# PDM.net
KiCad netlist of a schematic drawn in EAGLE
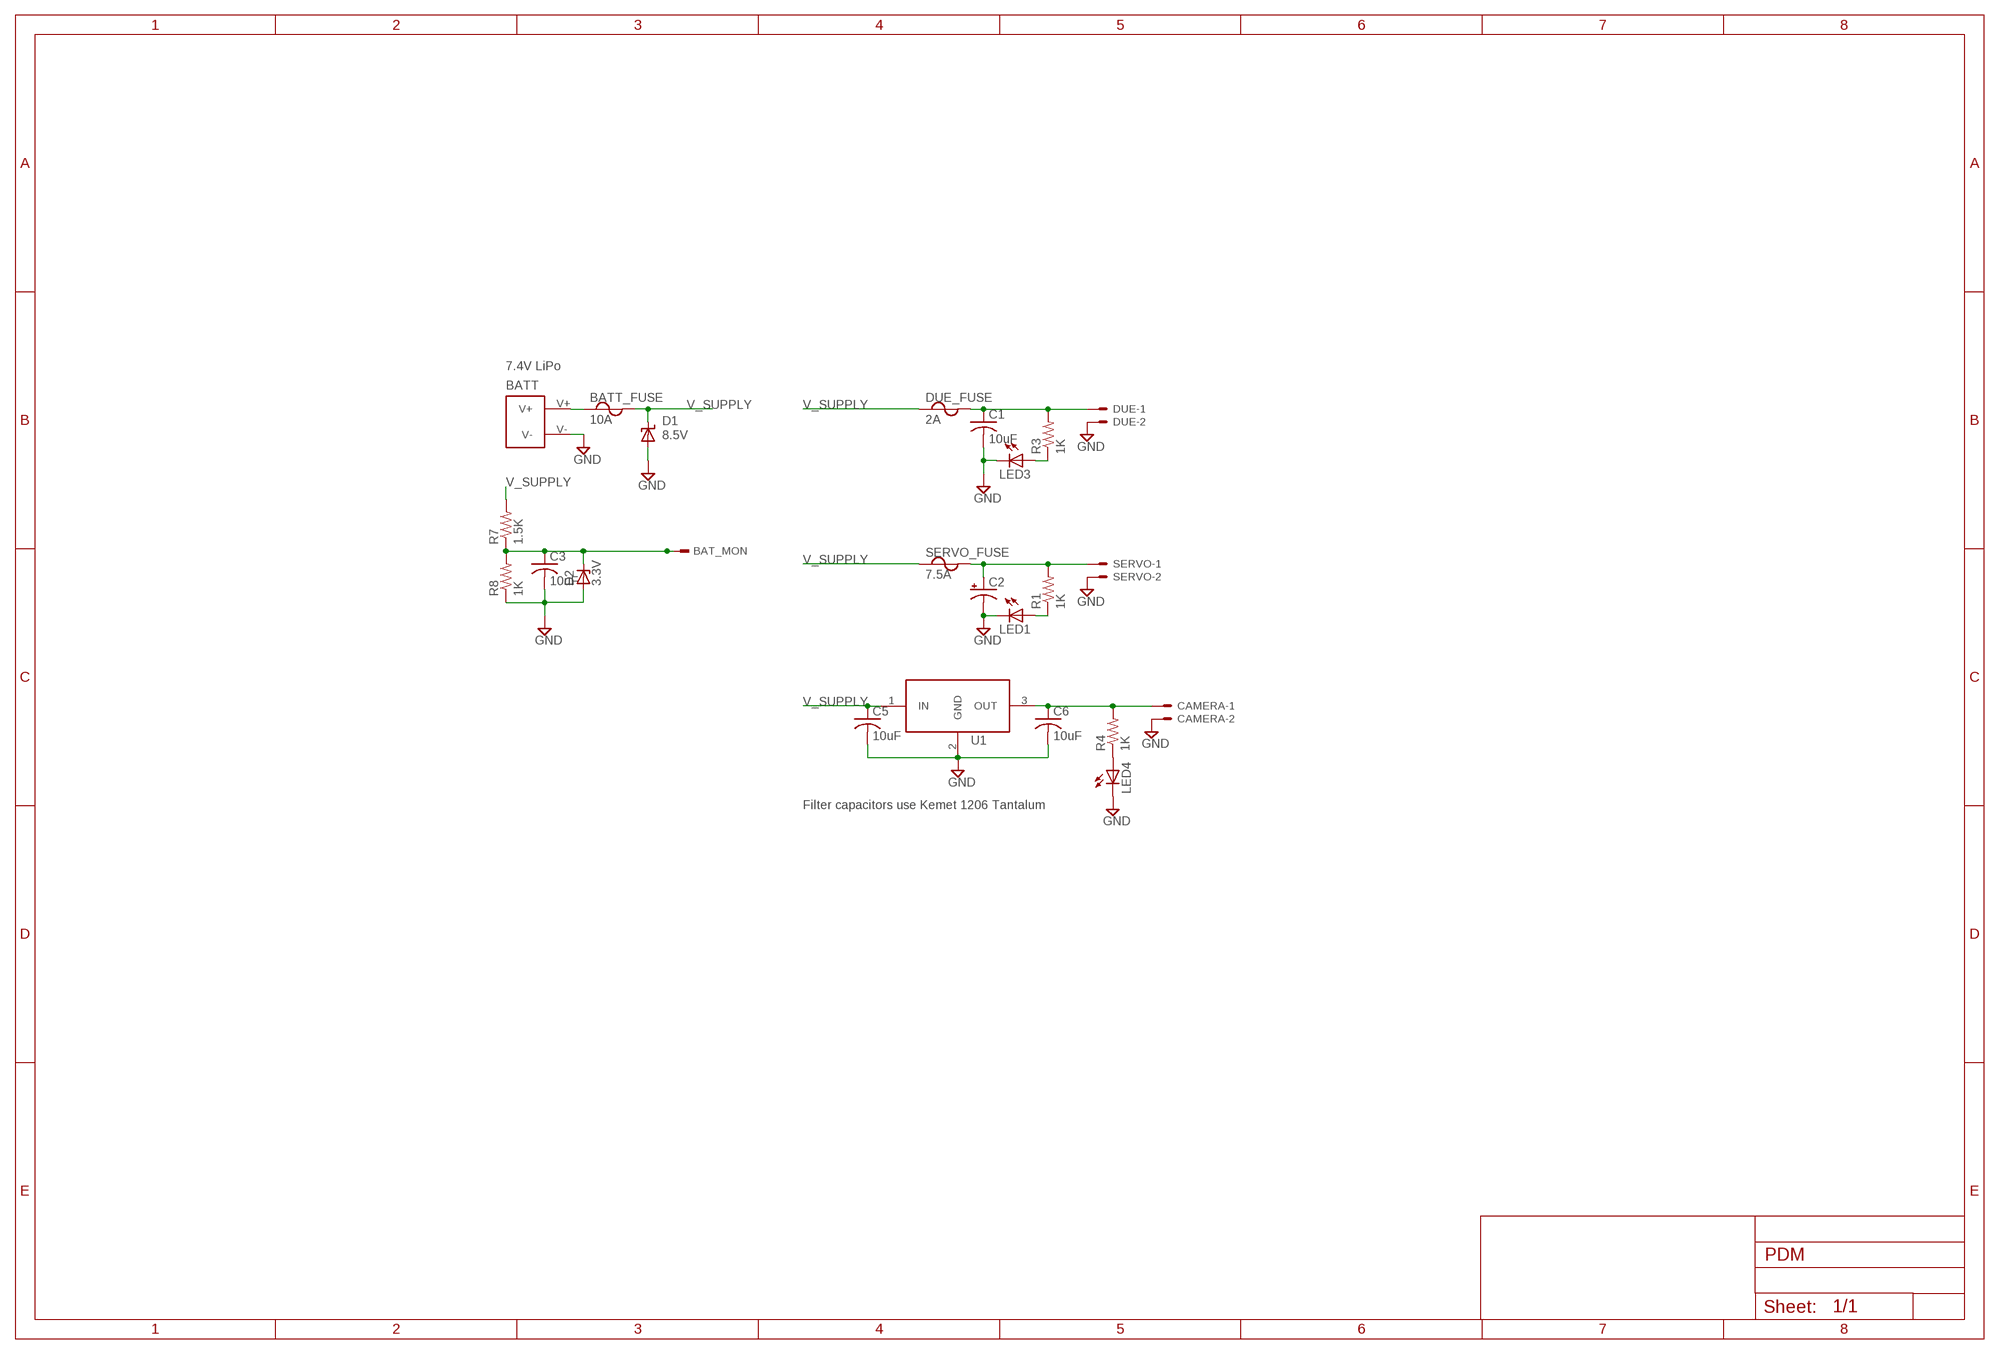
[diagram p0: schematic, sheet 1]

(export (version "E")
  (design (tool "Eeschema 10.0.6"))
  (components
    (comp (ref "BATT")
      (value "CON_XT60-")
      (footprint "eagle-import:CON_XT60_PCB_MALE")
      (libsource (lib "eagle-import") (part "CON_XT60-"))
    )
    (comp (ref "BATT_FUSE")
      (value "10A")
      (footprint "eagle-import:MINI_ATO")
      (libsource (lib "eagle-import") (part "FUSE-"))
    )
    (comp (ref "BAT_MON")
      (value "TSW-101-02-S-S")
      (footprint "eagle-import:TSW-101-02-S-S")
      (libsource (lib "eagle-import") (part "TSW-101-02-S-S"))
    )
    (comp (ref "C1")
      (value "10uF")
      (footprint "eagle-import:C1206K")
      (libsource (lib "eagle-import") (part "C-USC1206K"))
    )
    (comp (ref "C2")
      (value "CPOL-USTT5D11")
      (footprint "eagle-import:TT5D11")
      (libsource (lib "eagle-import") (part "CPOL-USTT5D11"))
    )
    (comp (ref "C3")
      (value "10uF")
      (footprint "eagle-import:C1206K")
      (libsource (lib "eagle-import") (part "C-USC1206K"))
    )
    (comp (ref "C5")
      (value "10uF")
      (footprint "eagle-import:C1206K")
      (libsource (lib "eagle-import") (part "C-USC1206K"))
    )
    (comp (ref "C6")
      (value "10uF")
      (footprint "eagle-import:C1206K")
      (libsource (lib "eagle-import") (part "C-USC1206K"))
    )
    (comp (ref "CAMERA")
      (value "5566-2")
      (footprint "eagle-import:5566-2")
      (libsource (lib "eagle-import") (part "5566-2"))
    )
    (comp (ref "D1")
      (value "8.5V")
      (footprint "eagle-import:SMBJ")
      (libsource (lib "eagle-import") (part "SUPPRESSOR-SMBJ"))
    )
    (comp (ref "D2")
      (value "3.3V")
      (footprint "eagle-import:SOD80C")
      (libsource (lib "eagle-import") (part "ZENER-DIODESOD80C"))
    )
    (comp (ref "DUE")
      (value "5566-2")
      (footprint "eagle-import:5566-2")
      (libsource (lib "eagle-import") (part "5566-2"))
    )
    (comp (ref "DUE_FUSE")
      (value "2A")
      (footprint "eagle-import:MINI_ATO")
      (libsource (lib "eagle-import") (part "FUSE-"))
    )
    (comp (ref "LED1")
      (value "LEDSML1206")
      (footprint "eagle-import:SML1206")
      (libsource (lib "eagle-import") (part "LEDSML1206"))
    )
    (comp (ref "LED3")
      (value "LEDSML1206")
      (footprint "eagle-import:SML1206")
      (libsource (lib "eagle-import") (part "LEDSML1206"))
    )
    (comp (ref "LED4")
      (value "LEDSML1206")
      (footprint "eagle-import:SML1206")
      (libsource (lib "eagle-import") (part "LEDSML1206"))
    )
    (comp (ref "R1")
      (value "1K")
      (footprint "eagle-import:R1206")
      (libsource (lib "eagle-import") (part "R-US_R1206"))
    )
    (comp (ref "R3")
      (value "1K")
      (footprint "eagle-import:R1206")
      (libsource (lib "eagle-import") (part "R-US_R1206"))
    )
    (comp (ref "R4")
      (value "1K")
      (footprint "eagle-import:R1206")
      (libsource (lib "eagle-import") (part "R-US_R1206"))
    )
    (comp (ref "R7")
      (value "1.5K")
      (footprint "eagle-import:R1206")
      (libsource (lib "eagle-import") (part "R-US_R1206"))
    )
    (comp (ref "R8")
      (value "1K")
      (footprint "eagle-import:R1206")
      (libsource (lib "eagle-import") (part "R-US_R1206"))
    )
    (comp (ref "SERVO")
      (value "5566-2")
      (footprint "eagle-import:5566-2")
      (libsource (lib "eagle-import") (part "5566-2"))
    )
    (comp (ref "SERVO_FUSE")
      (value "7.5A")
      (footprint "eagle-import:MINI_ATO")
      (libsource (lib "eagle-import") (part "FUSE-"))
    )
    (comp (ref "U1")
      (value "MIC29150/29300/29500VERTICAL")
      (footprint "eagle-import:TO220V")
      (libsource (lib "eagle-import") (part "MIC29150/29300/29500VERTICAL"))
    )
  )
  (nets
    (net (code "1") (name "/V_SUPPLY") (class "Default")
      (node (ref "BATT_FUSE") (pin "P$3") (pinfunction "2_P$3") (pintype "passive"))
      (node (ref "C5") (pin "1") (pinfunction "1_1") (pintype "passive"))
      (node (ref "D1") (pin "C") (pinfunction "C_C") (pintype "passive"))
      (node (ref "DUE_FUSE") (pin "P$2") (pinfunction "1_P$2") (pintype "passive"))
      (node (ref "R7") (pin "2") (pinfunction "2_2") (pintype "passive"))
      (node (ref "SERVO_FUSE") (pin "P$2") (pinfunction "1_P$2") (pintype "passive"))
      (node (ref "U1") (pin "1") (pinfunction "IN_1") (pintype "bidirectional"))
    )
    (net (code "2") (name "GND") (class "Default")
      (node (ref "BATT") (pin "V-") (pinfunction "V-_V-") (pintype "bidirectional"))
      (node (ref "C1") (pin "2") (pinfunction "2_2") (pintype "passive"))
      (node (ref "C2") (pin "-") (pinfunction "-_-") (pintype "passive"))
      (node (ref "C3") (pin "2") (pinfunction "2_2") (pintype "passive"))
      (node (ref "C5") (pin "2") (pinfunction "2_2") (pintype "passive"))
      (node (ref "C6") (pin "2") (pinfunction "2_2") (pintype "passive"))
      (node (ref "CAMERA") (pin "2") (pinfunction "S_2") (pintype "passive"))
      (node (ref "D1") (pin "A") (pinfunction "A_A") (pintype "passive"))
      (node (ref "D2") (pin "A") (pinfunction "A_A") (pintype "passive"))
      (node (ref "DUE") (pin "2") (pinfunction "S_2") (pintype "passive"))
      (node (ref "LED1") (pin "C") (pinfunction "C_C") (pintype "passive"))
      (node (ref "LED3") (pin "C") (pinfunction "C_C") (pintype "passive"))
      (node (ref "LED4") (pin "C") (pinfunction "C_C") (pintype "passive"))
      (node (ref "R8") (pin "1") (pinfunction "1_1") (pintype "passive"))
      (node (ref "SERVO") (pin "2") (pinfunction "S_2") (pintype "passive"))
      (node (ref "U1") (pin "2") (pinfunction "GND_2") (pintype "bidirectional"))
    )
    (net (code "3") (name "Net-(BATT_FUSE-1)") (class "Default")
      (node (ref "BATT") (pin "V+") (pinfunction "V+_V+") (pintype "bidirectional"))
      (node (ref "BATT_FUSE") (pin "P$2") (pinfunction "1_P$2") (pintype "passive"))
    )
    (net (code "4") (name "Net-(BAT_MON-Pad1)") (class "Default")
      (node (ref "BAT_MON") (pin "1") (pinfunction "1_1") (pintype "passive"))
      (node (ref "C3") (pin "1") (pinfunction "1_1") (pintype "passive"))
      (node (ref "D2") (pin "C") (pinfunction "C_C") (pintype "passive"))
      (node (ref "R7") (pin "1") (pinfunction "1_1") (pintype "passive"))
      (node (ref "R8") (pin "2") (pinfunction "2_2") (pintype "passive"))
    )
    (net (code "5") (name "Net-(CAMERAA-S)") (class "Default")
      (node (ref "C6") (pin "1") (pinfunction "1_1") (pintype "passive"))
      (node (ref "CAMERA") (pin "1") (pinfunction "S_1") (pintype "passive"))
      (node (ref "R4") (pin "2") (pinfunction "2_2") (pintype "passive"))
      (node (ref "U1") (pin "3") (pinfunction "OUT_3") (pintype "bidirectional"))
    )
    (net (code "6") (name "Net-(DUEA-S)") (class "Default")
      (node (ref "C1") (pin "1") (pinfunction "1_1") (pintype "passive"))
      (node (ref "DUE") (pin "1") (pinfunction "S_1") (pintype "passive"))
      (node (ref "DUE_FUSE") (pin "P$3") (pinfunction "2_P$3") (pintype "passive"))
      (node (ref "R3") (pin "2") (pinfunction "2_2") (pintype "passive"))
    )
    (net (code "7") (name "Net-(LED1-PadA)") (class "Default")
      (node (ref "LED1") (pin "A") (pinfunction "A_A") (pintype "passive"))
      (node (ref "R1") (pin "1") (pinfunction "1_1") (pintype "passive"))
    )
    (net (code "8") (name "Net-(LED3-PadA)") (class "Default")
      (node (ref "LED3") (pin "A") (pinfunction "A_A") (pintype "passive"))
      (node (ref "R3") (pin "1") (pinfunction "1_1") (pintype "passive"))
    )
    (net (code "9") (name "Net-(LED4-PadA)") (class "Default")
      (node (ref "LED4") (pin "A") (pinfunction "A_A") (pintype "passive"))
      (node (ref "R4") (pin "1") (pinfunction "1_1") (pintype "passive"))
    )
    (net (code "10") (name "Net-(SERVOA-S)") (class "Default")
      (node (ref "C2") (pin "+") (pinfunction "+_+") (pintype "passive"))
      (node (ref "R1") (pin "2") (pinfunction "2_2") (pintype "passive"))
      (node (ref "SERVO") (pin "1") (pinfunction "S_1") (pintype "passive"))
      (node (ref "SERVO_FUSE") (pin "P$3") (pinfunction "2_P$3") (pintype "passive"))
    )
  )
)
